# mod_mixer_v0_3.net
KiCad netlist of a schematic drawn in EAGLE
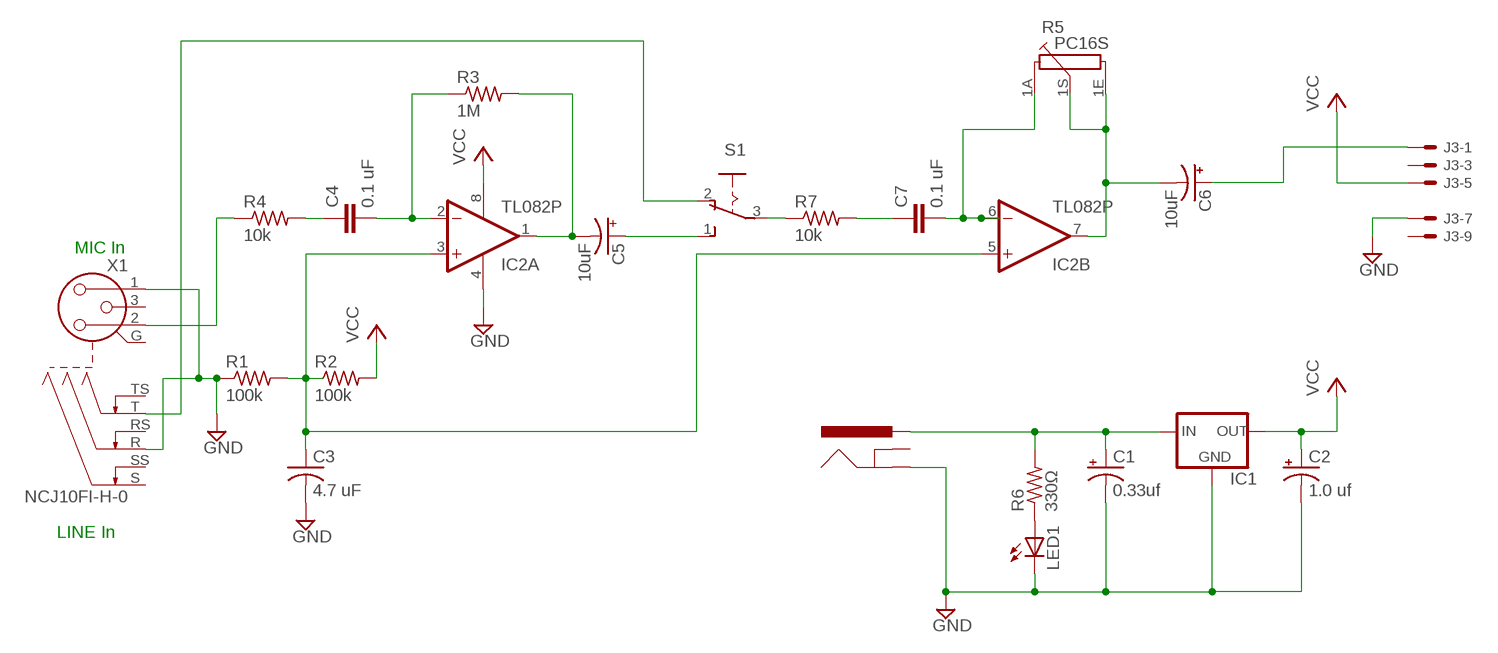
[diagram p0: schematic, sheet 1]

(export (version "E")
  (design (tool "Eeschema 10.0.6"))
  (components
    (comp (ref "C1")
      (value "0.33uf")
      (footprint "eagle-import:E2,5-6")
      (libsource (lib "eagle-import") (part "CPOL-USE2.5-6"))
    )
    (comp (ref "C2")
      (value "1.0 uf")
      (footprint "eagle-import:E2,5-6")
      (libsource (lib "eagle-import") (part "CPOL-USE2.5-6"))
    )
    (comp (ref "C3")
      (value "4.7 uF")
      (footprint "eagle-import:C050-030X075")
      (libsource (lib "eagle-import") (part "C-US050-030X075"))
    )
    (comp (ref "C4")
      (value "0.1 uF")
      (footprint "eagle-import:C5B2.5")
      (libsource (lib "eagle-import") (part "C5/2.5"))
    )
    (comp (ref "C5")
      (value "10uF")
      (footprint "eagle-import:E5-6")
      (libsource (lib "eagle-import") (part "CPOL-USE5-6"))
    )
    (comp (ref "C6")
      (value "10uF")
      (footprint "eagle-import:E2,5-7")
      (libsource (lib "eagle-import") (part "CPOL-USE2.5-7"))
    )
    (comp (ref "C7")
      (value "0.1 uF")
      (footprint "eagle-import:C5B2.5")
      (libsource (lib "eagle-import") (part "C5/2.5"))
    )
    (comp (ref "IC1")
      (value "V_REG_78XXSIDE")
      (footprint "eagle-import:78XXL")
      (libsource (lib "eagle-import") (part "V_REG_78XXSIDE"))
    )
    (comp (ref "IC2")
      (value "TL082P")
      (footprint "eagle-import:DIL08")
      (libsource (lib "eagle-import") (part "TL082P"))
    )
    (comp (ref "J1")
      (value "POWER_JACKSLT")
      (footprint "eagle-import:POWER_JACK_SLOT")
      (libsource (lib "eagle-import") (part "POWER_JACKSLT"))
    )
    (comp (ref "J3")
      (value "CON-50-EDGE")
      (footprint "eagle-import:CARDEDGE-50")
      (libsource (lib "eagle-import") (part "CON-50-EDGE"))
    )
    (comp (ref "LED1")
      (value "LEDSFH480")
      (footprint "eagle-import:SFH480")
      (libsource (lib "eagle-import") (part "LEDSFH480"))
    )
    (comp (ref "R1")
      (value "100k")
      (footprint "eagle-import:0207_10")
      (libsource (lib "eagle-import") (part "R-US_0207/10"))
    )
    (comp (ref "R2")
      (value "100k")
      (footprint "eagle-import:0207_10")
      (libsource (lib "eagle-import") (part "R-US_0207/10"))
    )
    (comp (ref "R3")
      (value "1M")
      (footprint "eagle-import:0207_10")
      (libsource (lib "eagle-import") (part "R-US_0207/10"))
    )
    (comp (ref "R4")
      (value "10k")
      (footprint "eagle-import:0207_10")
      (libsource (lib "eagle-import") (part "R-US_0207/10"))
    )
    (comp (ref "R5")
      (value "PC16S")
      (footprint "eagle-import:PC16S")
      (libsource (lib "eagle-import") (part "PC16S"))
    )
    (comp (ref "R6")
      (value "330Ω")
      (footprint "eagle-import:0207_10")
      (libsource (lib "eagle-import") (part "R-US_0207/10"))
    )
    (comp (ref "R7")
      (value "10k")
      (footprint "eagle-import:0207_10")
      (libsource (lib "eagle-import") (part "R-US_0207/10"))
    )
    (comp (ref "S1")
      (value "255SB")
      (footprint "eagle-import:255SB")
      (libsource (lib "eagle-import") (part "255SB"))
    )
    (comp (ref "X1")
      (value "NCJ10FI-H-0")
      (footprint "eagle-import:NCJ10FI-H-0")
      (libsource (lib "eagle-import") (part "NCJ10FI-H-0"))
    )
  )
  (nets
    (net (code "1") (name "GND") (class "Default")
      (node (ref "C1") (pin "-") (pinfunction "-_-") (pintype "passive"))
      (node (ref "C2") (pin "-") (pinfunction "-_-") (pintype "passive"))
      (node (ref "C3") (pin "2") (pinfunction "2_2") (pintype "passive"))
      (node (ref "IC1") (pin "GND") (pinfunction "GND_GND") (pintype "input"))
      (node (ref "IC2") (pin "4") (pinfunction "V-_4") (pintype "power_in"))
      (node (ref "J1") (pin "GND@2") (pinfunction "GND_GND@2") (pintype "bidirectional"))
      (node (ref "J3") (pin "7") (pinfunction "S_7") (pintype "passive"))
      (node (ref "LED1") (pin "K") (pinfunction "C_K") (pintype "passive"))
      (node (ref "R1") (pin "1") (pinfunction "1_1") (pintype "passive"))
      (node (ref "X1") (pin "1") (pinfunction "1_1") (pintype "passive"))
      (node (ref "X1") (pin "R") (pinfunction "R_R") (pintype "passive"))
    )
    (net (code "2") (name "Net-(C1-Pad+)") (class "Default")
      (node (ref "C1") (pin "+") (pinfunction "+_+") (pintype "passive"))
      (node (ref "IC1") (pin "IN") (pinfunction "IN_IN") (pintype "input"))
      (node (ref "J1") (pin "PWR") (pinfunction "PWR_PWR") (pintype "bidirectional"))
      (node (ref "R6") (pin "2") (pinfunction "2_2") (pintype "passive"))
    )
    (net (code "3") (name "Net-(C4-Pad1)") (class "Default")
      (node (ref "C4") (pin "1") (pinfunction "1_1") (pintype "passive"))
      (node (ref "R4") (pin "2") (pinfunction "2_2") (pintype "passive"))
    )
    (net (code "4") (name "Net-(C7-Pad1)") (class "Default")
      (node (ref "C7") (pin "1") (pinfunction "1_1") (pintype "passive"))
      (node (ref "R7") (pin "2") (pinfunction "2_2") (pintype "passive"))
    )
    (net (code "5") (name "Net-(IC2A-+IN)") (class "Default")
      (node (ref "C3") (pin "1") (pinfunction "1_1") (pintype "passive"))
      (node (ref "IC2") (pin "3") (pinfunction "+IN_3") (pintype "input"))
      (node (ref "IC2") (pin "5") (pinfunction "+IN_5") (pintype "input"))
      (node (ref "R1") (pin "2") (pinfunction "2_2") (pintype "passive"))
      (node (ref "R2") (pin "1") (pinfunction "1_1") (pintype "passive"))
    )
    (net (code "6") (name "Net-(IC2A--IN)") (class "Default")
      (node (ref "C4") (pin "2") (pinfunction "2_2") (pintype "passive"))
      (node (ref "IC2") (pin "2") (pinfunction "-IN_2") (pintype "input"))
      (node (ref "R3") (pin "1") (pinfunction "1_1") (pintype "passive"))
    )
    (net (code "7") (name "Net-(IC2A-OUT)") (class "Default")
      (node (ref "C5") (pin "-") (pinfunction "-_-") (pintype "passive"))
      (node (ref "IC2") (pin "1") (pinfunction "OUT_1") (pintype "output"))
      (node (ref "R3") (pin "2") (pinfunction "2_2") (pintype "passive"))
    )
    (net (code "8") (name "Net-(IC2B--IN)") (class "Default")
      (node (ref "C7") (pin "2") (pinfunction "2_2") (pintype "passive"))
      (node (ref "IC2") (pin "6") (pinfunction "-IN_6") (pintype "input"))
      (node (ref "R5") (pin "1A") (pinfunction "1A_1A") (pintype "passive"))
    )
    (net (code "9") (name "Net-(IC2B-OUT)") (class "Default")
      (node (ref "C6") (pin "-") (pinfunction "-_-") (pintype "passive"))
      (node (ref "IC2") (pin "7") (pinfunction "OUT_7") (pintype "output"))
      (node (ref "R5") (pin "1E") (pinfunction "1E_1E") (pintype "passive"))
      (node (ref "R5") (pin "1S") (pinfunction "1S_1S") (pintype "passive"))
    )
    (net (code "10") (name "Net-(J3A-S)") (class "Default")
      (node (ref "C6") (pin "+") (pinfunction "+_+") (pintype "passive"))
      (node (ref "J3") (pin "1") (pinfunction "S_1") (pintype "passive"))
    )
    (net (code "11") (name "Net-(LED1-PadA)") (class "Default")
      (node (ref "LED1") (pin "A") (pinfunction "A_A") (pintype "passive"))
      (node (ref "R6") (pin "1") (pinfunction "1_1") (pintype "passive"))
    )
    (net (code "12") (name "Net-(R4-Pad1)") (class "Default")
      (node (ref "R4") (pin "1") (pinfunction "1_1") (pintype "passive"))
      (node (ref "X1") (pin "2") (pinfunction "2_2") (pintype "passive"))
    )
    (net (code "13") (name "Net-(S1-O)") (class "Default")
      (node (ref "S1") (pin "2") (pinfunction "O_2") (pintype "passive"))
      (node (ref "X1") (pin "T") (pinfunction "T_T") (pintype "passive"))
    )
    (net (code "14") (name "Net-(S1-P)") (class "Default")
      (node (ref "R7") (pin "1") (pinfunction "1_1") (pintype "passive"))
      (node (ref "S1") (pin "3") (pinfunction "P_3") (pintype "passive"))
    )
    (net (code "15") (name "Net-(S1-S)") (class "Default")
      (node (ref "C5") (pin "+") (pinfunction "+_+") (pintype "passive"))
      (node (ref "S1") (pin "1") (pinfunction "S_1") (pintype "passive"))
    )
    (net (code "16") (name "VCC") (class "Default")
      (node (ref "C2") (pin "+") (pinfunction "+_+") (pintype "passive"))
      (node (ref "IC1") (pin "OUT") (pinfunction "OUT_OUT") (pintype "output"))
      (node (ref "IC2") (pin "8") (pinfunction "V+_8") (pintype "power_in"))
      (node (ref "J3") (pin "5") (pinfunction "S_5") (pintype "passive"))
      (node (ref "R2") (pin "2") (pinfunction "2_2") (pintype "passive"))
    )
    (net (code "17") (name "unconnected-(J1-GNDBREAK-PadGND@1)") (class "Default")
      (node (ref "J1") (pin "GND@1") (pinfunction "GNDBREAK_GND@1") (pintype "bidirectional"))
    )
    (net (code "18") (name "unconnected-(J3B-S-Pad3)") (class "Default")
      (node (ref "J3") (pin "3") (pinfunction "S_3") (pintype "passive"))
    )
    (net (code "19") (name "unconnected-(J3E-S-Pad9)") (class "Default")
      (node (ref "J3") (pin "9") (pinfunction "S_9") (pintype "passive"))
    )
    (net (code "20") (name "unconnected-(X1-Pad3)") (class "Default")
      (node (ref "X1") (pin "3") (pinfunction "3_3") (pintype "passive"))
    )
    (net (code "21") (name "unconnected-(X1-PadG)") (class "Default")
      (node (ref "X1") (pin "G") (pinfunction "G_G") (pintype "passive"))
    )
    (net (code "22") (name "unconnected-(X1-PadRS)") (class "Default")
      (node (ref "X1") (pin "RS") (pinfunction "RS_RS") (pintype "passive"))
    )
    (net (code "23") (name "unconnected-(X1-PadS)") (class "Default")
      (node (ref "X1") (pin "S") (pinfunction "S_S") (pintype "passive"))
    )
    (net (code "24") (name "unconnected-(X1-PadSS)") (class "Default")
      (node (ref "X1") (pin "SS") (pinfunction "SS_SS") (pintype "passive"))
    )
    (net (code "25") (name "unconnected-(X1-PadTS)") (class "Default")
      (node (ref "X1") (pin "TS") (pinfunction "TS_TS") (pintype "passive"))
    )
  )
)
